# Smart_IOT_v1.net
KiCad netlist of a schematic drawn in EAGLE
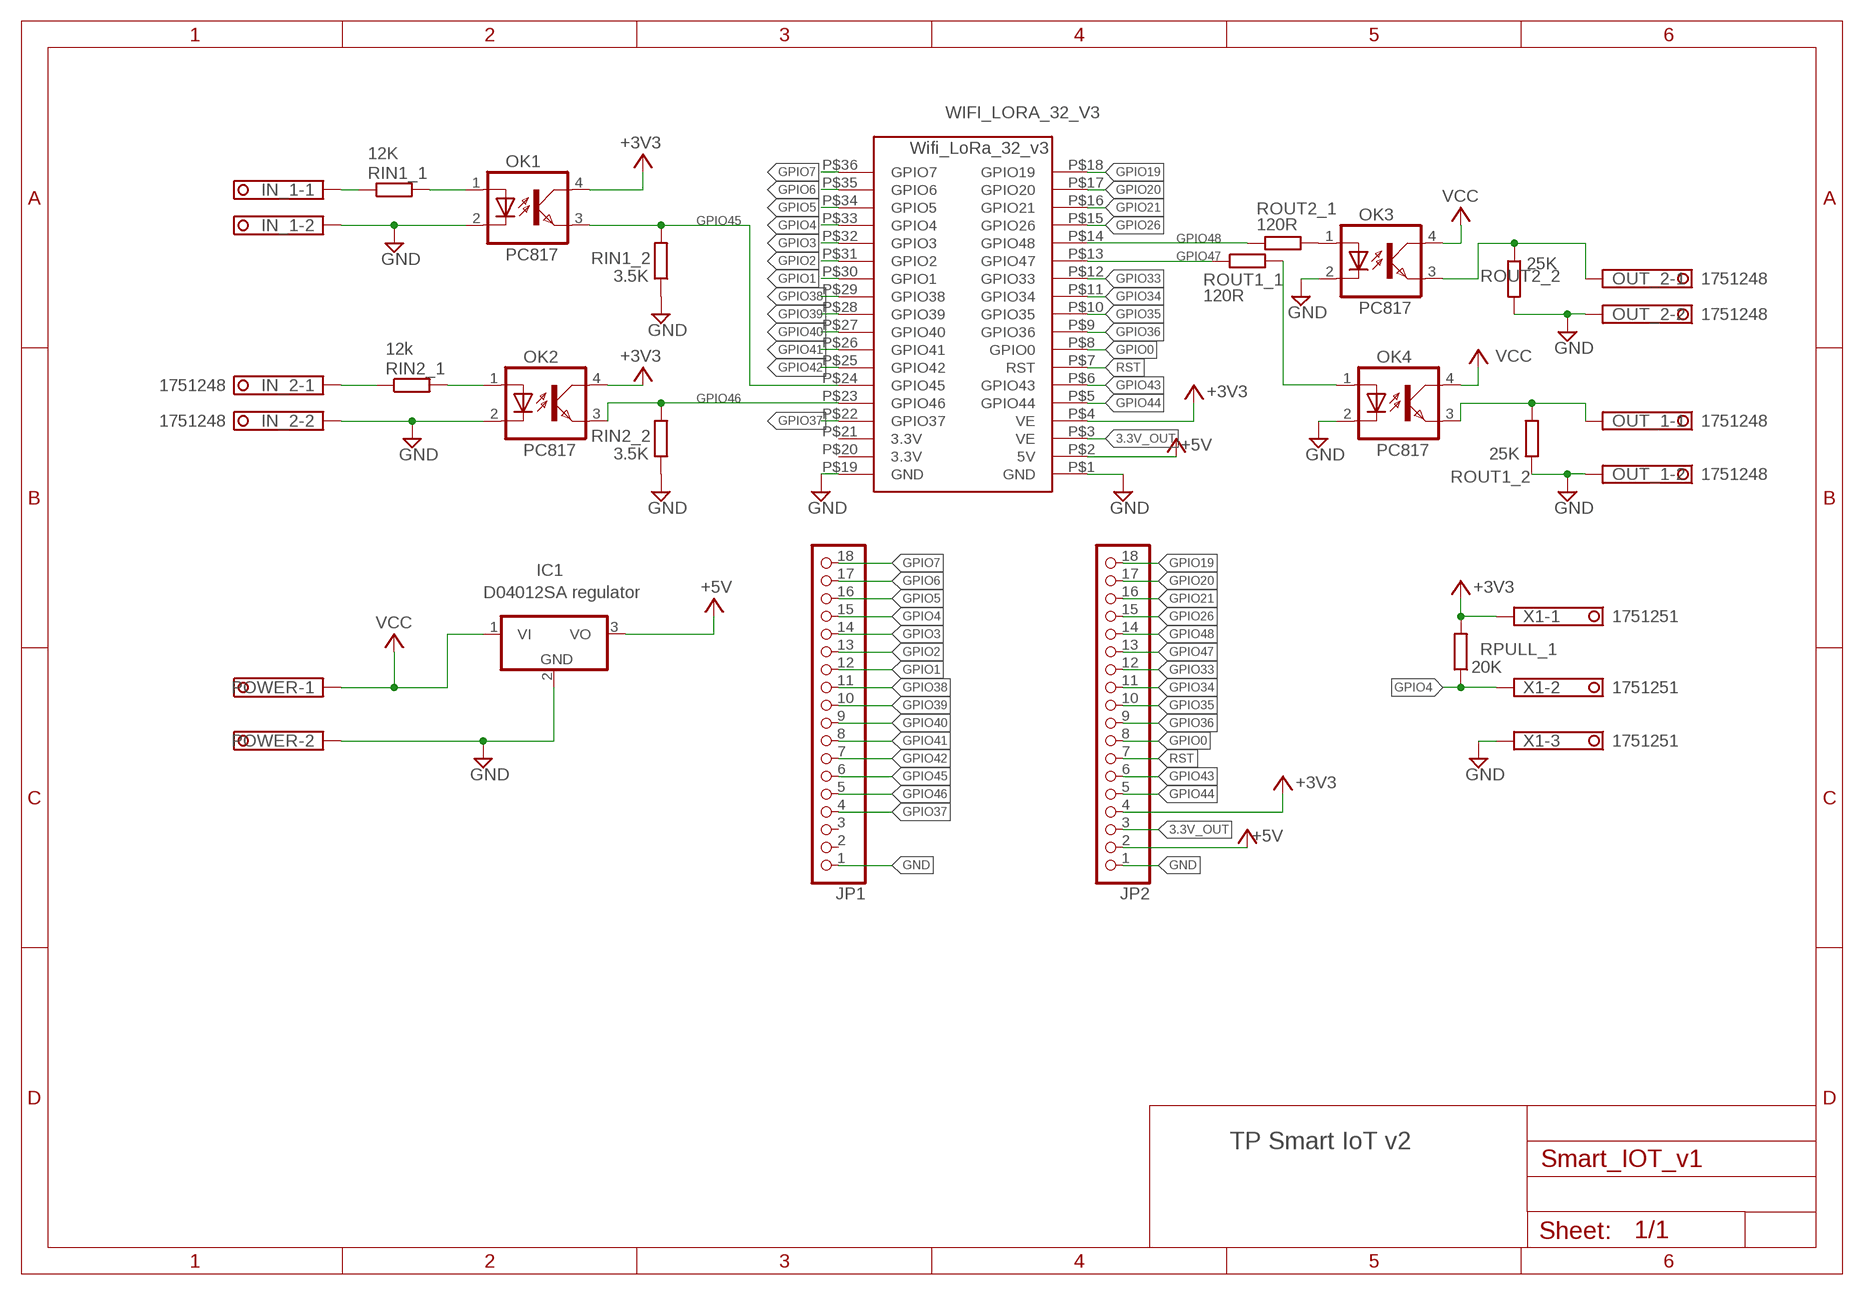
[diagram p0: schematic, sheet 1]

(export (version "E")
  (design (tool "Eeschema 10.0.6"))
  (components
    (comp (ref "IC1")
      (value "7805TV")
      (footprint "eagle-import:TO220V")
      (libsource (lib "eagle-import") (part "78TV05"))
    )
    (comp (ref "IN_1")
      (value "1751248")
      (footprint "eagle-import:1751248")
      (libsource (lib "eagle-import") (part "1751248"))
    )
    (comp (ref "IN_2")
      (value "1751248")
      (footprint "eagle-import:1751248")
      (libsource (lib "eagle-import") (part "1751248"))
    )
    (comp (ref "JP1")
      (value "PINHD-1X18")
      (footprint "eagle-import:1X18")
      (libsource (lib "eagle-import") (part "PINHD-1X18"))
    )
    (comp (ref "JP2")
      (value "PINHD-1X18")
      (footprint "eagle-import:1X18")
      (libsource (lib "eagle-import") (part "PINHD-1X18"))
    )
    (comp (ref "OK1")
      (value "PC817")
      (footprint "eagle-import:DIL04")
      (fields (field (name "MPN") "PC817X4J000F"))
      (libsource (lib "eagle-import") (part "PC817"))
    )
    (comp (ref "OK2")
      (value "PC817")
      (footprint "eagle-import:DIL04")
      (fields (field (name "MPN") "PC817X4J000F"))
      (libsource (lib "eagle-import") (part "PC817"))
    )
    (comp (ref "OK3")
      (value "PC817")
      (footprint "eagle-import:DIL04")
      (fields (field (name "MPN") "PC817X4J000F"))
      (libsource (lib "eagle-import") (part "PC817"))
    )
    (comp (ref "OK4")
      (value "PC817")
      (footprint "eagle-import:DIL04")
      (fields (field (name "MPN") "PC817X4J000F"))
      (libsource (lib "eagle-import") (part "PC817"))
    )
    (comp (ref "OUT_1")
      (value "1751248")
      (footprint "eagle-import:1751248")
      (libsource (lib "eagle-import") (part "1751248"))
    )
    (comp (ref "OUT_2")
      (value "1751248")
      (footprint "eagle-import:1751248")
      (libsource (lib "eagle-import") (part "1751248"))
    )
    (comp (ref "POWER")
      (value "1751248")
      (footprint "eagle-import:1751248")
      (libsource (lib "eagle-import") (part "1751248"))
    )
    (comp (ref "RIN1_1")
      (value "12K")
      (footprint "eagle-import:M1206")
      (libsource (lib "eagle-import") (part "R-EU_M1206"))
    )
    (comp (ref "RIN1_2")
      (value "3.5K")
      (footprint "eagle-import:M1206")
      (libsource (lib "eagle-import") (part "R-EU_M1206"))
    )
    (comp (ref "RIN2_1")
      (value "12k")
      (footprint "eagle-import:M1206")
      (libsource (lib "eagle-import") (part "R-EU_M1206"))
    )
    (comp (ref "RIN2_2")
      (value "3.5K")
      (footprint "eagle-import:M1206")
      (libsource (lib "eagle-import") (part "R-EU_M1206"))
    )
    (comp (ref "ROUT1_1")
      (value "120R")
      (footprint "eagle-import:M1206")
      (libsource (lib "eagle-import") (part "R-EU_M1206"))
    )
    (comp (ref "ROUT1_2")
      (value "25K")
      (footprint "eagle-import:M1206")
      (libsource (lib "eagle-import") (part "R-EU_M1206"))
    )
    (comp (ref "ROUT2_1")
      (value "120R")
      (footprint "eagle-import:M1206")
      (libsource (lib "eagle-import") (part "R-EU_M1206"))
    )
    (comp (ref "ROUT2_2")
      (value "25K")
      (footprint "eagle-import:M1206")
      (libsource (lib "eagle-import") (part "R-EU_M1206"))
    )
    (comp (ref "RPULL_1")
      (value "20K")
      (footprint "eagle-import:M1206")
      (libsource (lib "eagle-import") (part "R-EU_M1206"))
    )
    (comp (ref "WIFI_LORA_32_V3")
      (value "WIFI_LORA_32_V3")
      (footprint "eagle-import:WIFI_LORA_32_V3")
      (libsource (lib "eagle-import") (part "WIFI_LORA_32_V3"))
    )
    (comp (ref "X1")
      (value "1751251")
      (footprint "eagle-import:1751251")
      (libsource (lib "eagle-import") (part "1751251"))
    )
  )
  (nets
    (net (code "1") (name "+3V3") (class "Default")
      (node (ref "JP2") (pin "4") (pinfunction "4_4") (pintype "passive"))
      (node (ref "OK1") (pin "4") (pinfunction "COL_4") (pintype "passive"))
      (node (ref "OK2") (pin "4") (pinfunction "COL_4") (pintype "passive"))
      (node (ref "RPULL_1") (pin "2") (pinfunction "2_2") (pintype "passive"))
      (node (ref "WIFI_LORA_32_V3") (pin "P$4") (pinfunction "VE_P$4") (pintype "bidirectional"))
      (node (ref "X1") (pin "1") (pinfunction "K_1") (pintype "passive"))
    )
    (net (code "2") (name "+5V") (class "Default")
      (node (ref "IC1") (pin "3") (pinfunction "VO_3") (pintype "passive"))
      (node (ref "JP2") (pin "2") (pinfunction "2_2") (pintype "passive"))
      (node (ref "WIFI_LORA_32_V3") (pin "P$2") (pinfunction "5V_P$2") (pintype "bidirectional"))
    )
    (net (code "3") (name "3.3V_OUT") (class "Default")
      (node (ref "JP2") (pin "3") (pinfunction "3_3") (pintype "passive"))
      (node (ref "WIFI_LORA_32_V3") (pin "P$3") (pinfunction "VE_P$3") (pintype "bidirectional"))
    )
    (net (code "4") (name "GND") (class "Default")
      (node (ref "IC1") (pin "2") (pinfunction "GND_2") (pintype "passive"))
      (node (ref "IN_1") (pin "2") (pinfunction "K_2") (pintype "passive"))
      (node (ref "IN_2") (pin "2") (pinfunction "K_2") (pintype "passive"))
      (node (ref "JP1") (pin "1") (pinfunction "1_1") (pintype "passive"))
      (node (ref "JP2") (pin "1") (pinfunction "1_1") (pintype "passive"))
      (node (ref "OK1") (pin "2") (pinfunction "C_2") (pintype "passive"))
      (node (ref "OK2") (pin "2") (pinfunction "C_2") (pintype "passive"))
      (node (ref "OK3") (pin "2") (pinfunction "C_2") (pintype "passive"))
      (node (ref "OK4") (pin "2") (pinfunction "C_2") (pintype "passive"))
      (node (ref "OUT_1") (pin "2") (pinfunction "K_2") (pintype "passive"))
      (node (ref "OUT_2") (pin "2") (pinfunction "K_2") (pintype "passive"))
      (node (ref "POWER") (pin "2") (pinfunction "K_2") (pintype "passive"))
      (node (ref "RIN1_2") (pin "1") (pinfunction "1_1") (pintype "passive"))
      (node (ref "RIN2_2") (pin "1") (pinfunction "1_1") (pintype "passive"))
      (node (ref "ROUT1_2") (pin "1") (pinfunction "1_1") (pintype "passive"))
      (node (ref "ROUT2_2") (pin "2") (pinfunction "2_2") (pintype "passive"))
      (node (ref "WIFI_LORA_32_V3") (pin "P$1") (pinfunction "GND_P$1") (pintype "bidirectional"))
      (node (ref "WIFI_LORA_32_V3") (pin "P$19") (pinfunction "GND_P$19") (pintype "bidirectional"))
      (node (ref "X1") (pin "3") (pinfunction "K_3") (pintype "passive"))
    )
    (net (code "5") (name "GPIO0") (class "Default")
      (node (ref "JP2") (pin "8") (pinfunction "8_8") (pintype "passive"))
      (node (ref "WIFI_LORA_32_V3") (pin "P$8") (pinfunction "GPIO0_P$8") (pintype "bidirectional"))
    )
    (net (code "6") (name "GPIO1") (class "Default")
      (node (ref "JP1") (pin "12") (pinfunction "12_12") (pintype "passive"))
      (node (ref "WIFI_LORA_32_V3") (pin "P$30") (pinfunction "GPIO1_P$30") (pintype "bidirectional"))
    )
    (net (code "7") (name "GPIO2") (class "Default")
      (node (ref "JP1") (pin "13") (pinfunction "13_13") (pintype "passive"))
      (node (ref "WIFI_LORA_32_V3") (pin "P$31") (pinfunction "GPIO2_P$31") (pintype "bidirectional"))
    )
    (net (code "8") (name "GPIO3") (class "Default")
      (node (ref "JP1") (pin "14") (pinfunction "14_14") (pintype "passive"))
      (node (ref "WIFI_LORA_32_V3") (pin "P$32") (pinfunction "GPIO3_P$32") (pintype "bidirectional"))
    )
    (net (code "9") (name "GPIO4") (class "Default")
      (node (ref "JP1") (pin "15") (pinfunction "15_15") (pintype "passive"))
      (node (ref "RPULL_1") (pin "1") (pinfunction "1_1") (pintype "passive"))
      (node (ref "WIFI_LORA_32_V3") (pin "P$33") (pinfunction "GPIO4_P$33") (pintype "bidirectional"))
      (node (ref "X1") (pin "2") (pinfunction "K_2") (pintype "passive"))
    )
    (net (code "10") (name "GPIO5") (class "Default")
      (node (ref "JP1") (pin "16") (pinfunction "16_16") (pintype "passive"))
      (node (ref "WIFI_LORA_32_V3") (pin "P$34") (pinfunction "GPIO5_P$34") (pintype "bidirectional"))
    )
    (net (code "11") (name "GPIO6") (class "Default")
      (node (ref "JP1") (pin "17") (pinfunction "17_17") (pintype "passive"))
      (node (ref "WIFI_LORA_32_V3") (pin "P$35") (pinfunction "GPIO6_P$35") (pintype "bidirectional"))
    )
    (net (code "12") (name "GPIO7") (class "Default")
      (node (ref "JP1") (pin "18") (pinfunction "18_18") (pintype "passive"))
      (node (ref "WIFI_LORA_32_V3") (pin "P$36") (pinfunction "GPIO7_P$36") (pintype "bidirectional"))
    )
    (net (code "13") (name "GPIO19") (class "Default")
      (node (ref "JP2") (pin "18") (pinfunction "18_18") (pintype "passive"))
      (node (ref "WIFI_LORA_32_V3") (pin "P$18") (pinfunction "GPIO19_P$18") (pintype "bidirectional"))
    )
    (net (code "14") (name "GPIO20") (class "Default")
      (node (ref "JP2") (pin "17") (pinfunction "17_17") (pintype "passive"))
      (node (ref "WIFI_LORA_32_V3") (pin "P$17") (pinfunction "GPIO20_P$17") (pintype "bidirectional"))
    )
    (net (code "15") (name "GPIO21") (class "Default")
      (node (ref "JP2") (pin "16") (pinfunction "16_16") (pintype "passive"))
      (node (ref "WIFI_LORA_32_V3") (pin "P$16") (pinfunction "GPIO21_P$16") (pintype "bidirectional"))
    )
    (net (code "16") (name "GPIO26") (class "Default")
      (node (ref "JP2") (pin "15") (pinfunction "15_15") (pintype "passive"))
      (node (ref "WIFI_LORA_32_V3") (pin "P$15") (pinfunction "GPIO26_P$15") (pintype "bidirectional"))
    )
    (net (code "17") (name "GPIO33") (class "Default")
      (node (ref "JP2") (pin "12") (pinfunction "12_12") (pintype "passive"))
      (node (ref "WIFI_LORA_32_V3") (pin "P$12") (pinfunction "GPIO33_P$12") (pintype "bidirectional"))
    )
    (net (code "18") (name "GPIO34") (class "Default")
      (node (ref "JP2") (pin "11") (pinfunction "11_11") (pintype "passive"))
      (node (ref "WIFI_LORA_32_V3") (pin "P$11") (pinfunction "GPIO34_P$11") (pintype "bidirectional"))
    )
    (net (code "19") (name "GPIO35") (class "Default")
      (node (ref "JP2") (pin "10") (pinfunction "10_10") (pintype "passive"))
      (node (ref "WIFI_LORA_32_V3") (pin "P$10") (pinfunction "GPIO35_P$10") (pintype "bidirectional"))
    )
    (net (code "20") (name "GPIO36") (class "Default")
      (node (ref "JP2") (pin "9") (pinfunction "9_9") (pintype "passive"))
      (node (ref "WIFI_LORA_32_V3") (pin "P$9") (pinfunction "GPIO36_P$9") (pintype "bidirectional"))
    )
    (net (code "21") (name "GPIO37") (class "Default")
      (node (ref "JP1") (pin "4") (pinfunction "4_4") (pintype "passive"))
      (node (ref "WIFI_LORA_32_V3") (pin "P$22") (pinfunction "GPIO37_P$22") (pintype "bidirectional"))
    )
    (net (code "22") (name "GPIO38") (class "Default")
      (node (ref "JP1") (pin "11") (pinfunction "11_11") (pintype "passive"))
      (node (ref "WIFI_LORA_32_V3") (pin "P$29") (pinfunction "GPIO38_P$29") (pintype "bidirectional"))
    )
    (net (code "23") (name "GPIO39") (class "Default")
      (node (ref "JP1") (pin "10") (pinfunction "10_10") (pintype "passive"))
      (node (ref "WIFI_LORA_32_V3") (pin "P$28") (pinfunction "GPIO39_P$28") (pintype "bidirectional"))
    )
    (net (code "24") (name "GPIO40") (class "Default")
      (node (ref "JP1") (pin "9") (pinfunction "9_9") (pintype "passive"))
      (node (ref "WIFI_LORA_32_V3") (pin "P$27") (pinfunction "GPIO40_P$27") (pintype "bidirectional"))
    )
    (net (code "25") (name "GPIO41") (class "Default")
      (node (ref "JP1") (pin "8") (pinfunction "8_8") (pintype "passive"))
      (node (ref "WIFI_LORA_32_V3") (pin "P$26") (pinfunction "GPIO41_P$26") (pintype "bidirectional"))
    )
    (net (code "26") (name "GPIO42") (class "Default")
      (node (ref "JP1") (pin "7") (pinfunction "7_7") (pintype "passive"))
      (node (ref "WIFI_LORA_32_V3") (pin "P$25") (pinfunction "GPIO42_P$25") (pintype "bidirectional"))
    )
    (net (code "27") (name "GPIO43") (class "Default")
      (node (ref "JP2") (pin "6") (pinfunction "6_6") (pintype "passive"))
      (node (ref "WIFI_LORA_32_V3") (pin "P$6") (pinfunction "GPIO43_P$6") (pintype "bidirectional"))
    )
    (net (code "28") (name "GPIO44") (class "Default")
      (node (ref "JP2") (pin "5") (pinfunction "5_5") (pintype "passive"))
      (node (ref "WIFI_LORA_32_V3") (pin "P$5") (pinfunction "GPIO44_P$5") (pintype "bidirectional"))
    )
    (net (code "29") (name "GPIO45") (class "Default")
      (node (ref "JP1") (pin "6") (pinfunction "6_6") (pintype "passive"))
      (node (ref "OK1") (pin "3") (pinfunction "EMIT_3") (pintype "passive"))
      (node (ref "RIN1_2") (pin "2") (pinfunction "2_2") (pintype "passive"))
      (node (ref "WIFI_LORA_32_V3") (pin "P$24") (pinfunction "GPIO45_P$24") (pintype "bidirectional"))
    )
    (net (code "30") (name "GPIO46") (class "Default")
      (node (ref "JP1") (pin "5") (pinfunction "5_5") (pintype "passive"))
      (node (ref "OK2") (pin "3") (pinfunction "EMIT_3") (pintype "passive"))
      (node (ref "RIN2_2") (pin "2") (pinfunction "2_2") (pintype "passive"))
      (node (ref "WIFI_LORA_32_V3") (pin "P$23") (pinfunction "GPIO46_P$23") (pintype "bidirectional"))
    )
    (net (code "31") (name "GPIO47") (class "Default")
      (node (ref "JP2") (pin "13") (pinfunction "13_13") (pintype "passive"))
      (node (ref "ROUT1_1") (pin "1") (pinfunction "1_1") (pintype "passive"))
      (node (ref "WIFI_LORA_32_V3") (pin "P$13") (pinfunction "GPIO47_P$13") (pintype "bidirectional"))
    )
    (net (code "32") (name "GPIO48") (class "Default")
      (node (ref "JP2") (pin "14") (pinfunction "14_14") (pintype "passive"))
      (node (ref "ROUT2_1") (pin "1") (pinfunction "1_1") (pintype "passive"))
      (node (ref "WIFI_LORA_32_V3") (pin "P$14") (pinfunction "GPIO48_P$14") (pintype "bidirectional"))
    )
    (net (code "33") (name "Net-(IN_1A-K)") (class "Default")
      (node (ref "IN_1") (pin "1") (pinfunction "K_1") (pintype "passive"))
      (node (ref "RIN1_1") (pin "1") (pinfunction "1_1") (pintype "passive"))
    )
    (net (code "34") (name "Net-(IN_2A-K)") (class "Default")
      (node (ref "IN_2") (pin "1") (pinfunction "K_1") (pintype "passive"))
      (node (ref "RIN2_1") (pin "1") (pinfunction "1_1") (pintype "passive"))
    )
    (net (code "35") (name "Net-(OK1-A)") (class "Default")
      (node (ref "OK1") (pin "1") (pinfunction "A_1") (pintype "passive"))
      (node (ref "RIN1_1") (pin "2") (pinfunction "2_2") (pintype "passive"))
    )
    (net (code "36") (name "Net-(OK2-A)") (class "Default")
      (node (ref "OK2") (pin "1") (pinfunction "A_1") (pintype "passive"))
      (node (ref "RIN2_1") (pin "2") (pinfunction "2_2") (pintype "passive"))
    )
    (net (code "37") (name "Net-(OK3-A)") (class "Default")
      (node (ref "OK3") (pin "1") (pinfunction "A_1") (pintype "passive"))
      (node (ref "ROUT2_1") (pin "2") (pinfunction "2_2") (pintype "passive"))
    )
    (net (code "38") (name "Net-(OK3-EMIT)") (class "Default")
      (node (ref "OK3") (pin "3") (pinfunction "EMIT_3") (pintype "passive"))
      (node (ref "OUT_2") (pin "1") (pinfunction "K_1") (pintype "passive"))
      (node (ref "ROUT2_2") (pin "1") (pinfunction "1_1") (pintype "passive"))
    )
    (net (code "39") (name "Net-(OK4-A)") (class "Default")
      (node (ref "OK4") (pin "1") (pinfunction "A_1") (pintype "passive"))
      (node (ref "ROUT1_1") (pin "2") (pinfunction "2_2") (pintype "passive"))
    )
    (net (code "40") (name "Net-(OK4-EMIT)") (class "Default")
      (node (ref "OK4") (pin "3") (pinfunction "EMIT_3") (pintype "passive"))
      (node (ref "OUT_1") (pin "1") (pinfunction "K_1") (pintype "passive"))
      (node (ref "ROUT1_2") (pin "2") (pinfunction "2_2") (pintype "passive"))
    )
    (net (code "41") (name "RST") (class "Default")
      (node (ref "JP2") (pin "7") (pinfunction "7_7") (pintype "passive"))
      (node (ref "WIFI_LORA_32_V3") (pin "P$7") (pinfunction "RST_P$7") (pintype "bidirectional"))
    )
    (net (code "42") (name "VCC") (class "Default")
      (node (ref "IC1") (pin "1") (pinfunction "VI_1") (pintype "input"))
      (node (ref "OK3") (pin "4") (pinfunction "COL_4") (pintype "passive"))
      (node (ref "OK4") (pin "4") (pinfunction "COL_4") (pintype "passive"))
      (node (ref "POWER") (pin "1") (pinfunction "K_1") (pintype "passive"))
    )
    (net (code "43") (name "unconnected-(JP1-Pad2)") (class "Default")
      (node (ref "JP1") (pin "2") (pinfunction "2_2") (pintype "passive"))
    )
    (net (code "44") (name "unconnected-(JP1-Pad3)") (class "Default")
      (node (ref "JP1") (pin "3") (pinfunction "3_3") (pintype "passive"))
    )
    (net (code "45") (name "unconnected-(WIFI_LORA_32_V3-3.3V-PadP$20)") (class "Default")
      (node (ref "WIFI_LORA_32_V3") (pin "P$20") (pinfunction "3.3V_P$20") (pintype "bidirectional"))
    )
    (net (code "46") (name "unconnected-(WIFI_LORA_32_V3-3.3V-PadP$21)") (class "Default")
      (node (ref "WIFI_LORA_32_V3") (pin "P$21") (pinfunction "3.3V_P$21") (pintype "bidirectional"))
    )
  )
)
